# dac_blk.net
KiCad netlist of a schematic drawn in EAGLE
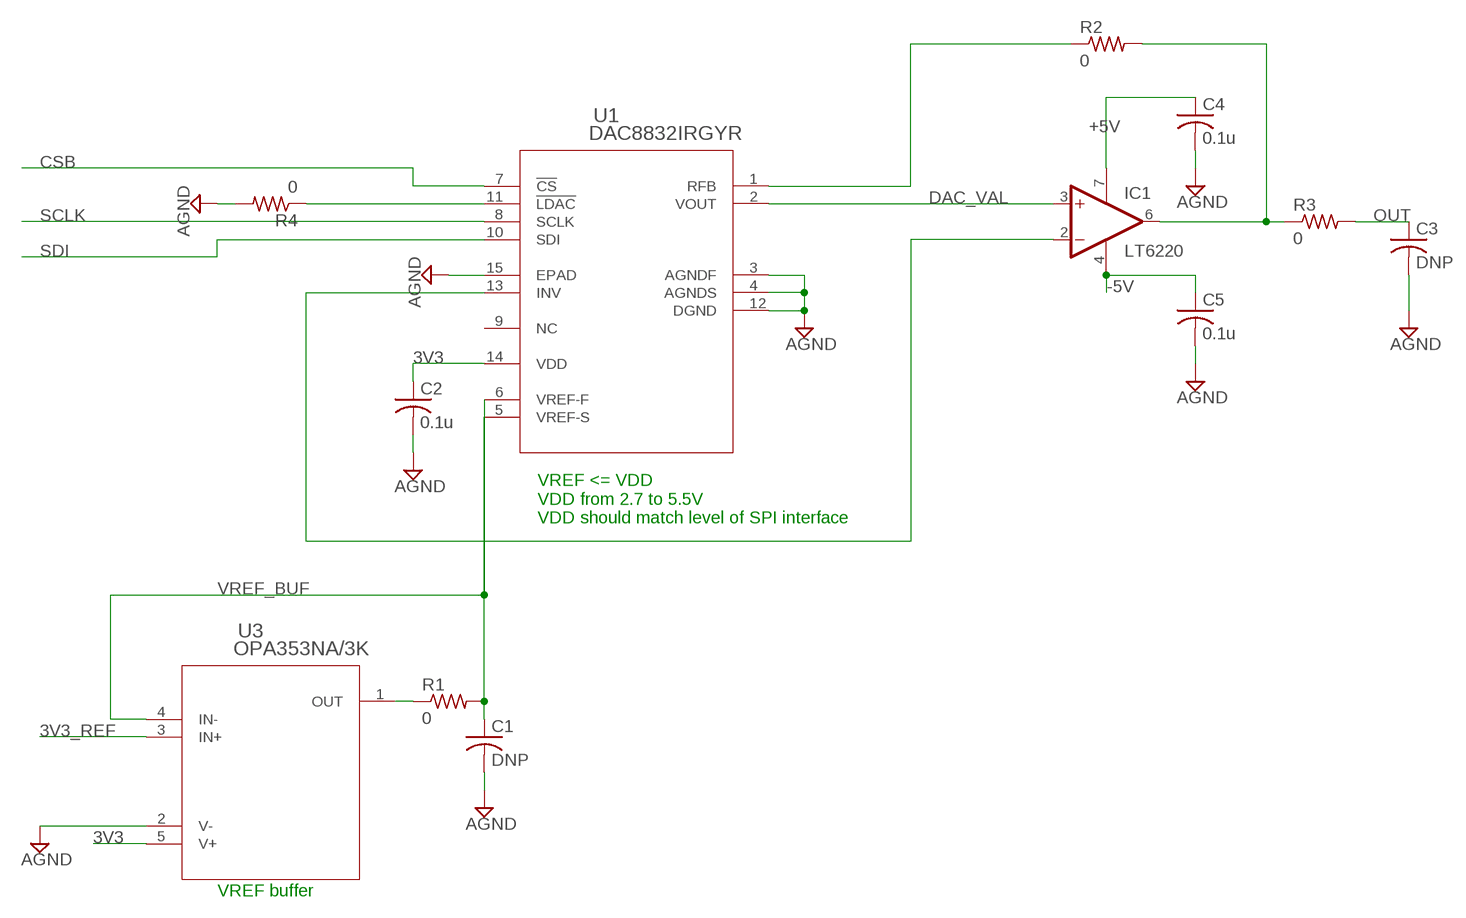
[diagram p0: schematic, sheet 1]

(export (version "E")
  (design (tool "Eeschema 10.0.6"))
  (components
    (comp (ref "C1")
      (value "DNP")
      (footprint "eagle-import:C0603")
      (libsource (lib "eagle-import") (part "C-USC0603"))
    )
    (comp (ref "C2")
      (value "0.1u")
      (footprint "eagle-import:C0603")
      (libsource (lib "eagle-import") (part "C-USC0603"))
    )
    (comp (ref "C3")
      (value "DNP")
      (footprint "eagle-import:C0603")
      (libsource (lib "eagle-import") (part "C-USC0603"))
    )
    (comp (ref "C4")
      (value "0.1u")
      (footprint "eagle-import:C0603")
      (libsource (lib "eagle-import") (part "C-USC0603"))
    )
    (comp (ref "C5")
      (value "0.1u")
      (footprint "eagle-import:C0603")
      (libsource (lib "eagle-import") (part "C-USC0603"))
    )
    (comp (ref "IC1")
      (value "LT6220")
      (footprint "eagle-import:SO08")
      (libsource (lib "eagle-import") (part "MCP601SN"))
    )
    (comp (ref "R1")
      (value "0")
      (footprint "eagle-import:R0603")
      (libsource (lib "eagle-import") (part "R-US_R0603"))
    )
    (comp (ref "R2")
      (value "0")
      (footprint "eagle-import:R0603")
      (libsource (lib "eagle-import") (part "R-US_R0603"))
    )
    (comp (ref "R3")
      (value "0")
      (footprint "eagle-import:R0603")
      (libsource (lib "eagle-import") (part "R-US_R0603"))
    )
    (comp (ref "R4")
      (value "0")
      (footprint "eagle-import:R0603")
      (libsource (lib "eagle-import") (part "R-US_R0603"))
    )
    (comp (ref "U1")
      (value "DAC8832IRGYR")
      (footprint "eagle-import:RGY14_2P05X2P05")
      (fields (field (name "MANUFACTURER") "Texas Instruments"))
      (libsource (lib "eagle-import") (part "DAC8832IRGYR"))
    )
    (comp (ref "U3")
      (value "OPA353NA/3K")
      (footprint "eagle-import:DBV5")
      (fields (field (name "MANUFACTURER") "Texas Instruments"))
      (libsource (lib "eagle-import") (part "OPA353NA/3K"))
    )
  )
  (nets
    (net (code "1") (name "/+5V") (class "Default")
      (node (ref "C4") (pin "1") (pinfunction "1_1") (pintype "passive"))
      (node (ref "IC1") (pin "7") (pinfunction "V+_7") (pintype "power_in"))
    )
    (net (code "2") (name "/-5V") (class "Default")
      (node (ref "C5") (pin "1") (pinfunction "1_1") (pintype "passive"))
      (node (ref "IC1") (pin "4") (pinfunction "V-_4") (pintype "power_in"))
    )
    (net (code "3") (name "/3V3") (class "Default")
      (node (ref "C2") (pin "1") (pinfunction "1_1") (pintype "passive"))
      (node (ref "U1") (pin "14") (pinfunction "VDD_14") (pintype "power_in"))
      (node (ref "U3") (pin "5") (pinfunction "V+_5") (pintype "power_in"))
    )
    (net (code "4") (name "/3V3_REF") (class "Default")
      (node (ref "U3") (pin "3") (pinfunction "IN+_3") (pintype "input"))
    )
    (net (code "5") (name "/CSB") (class "Default")
      (node (ref "U1") (pin "7") (pinfunction "~{CS}_7") (pintype "input"))
    )
    (net (code "6") (name "/DAC_VAL") (class "Default")
      (node (ref "IC1") (pin "3") (pinfunction "+IN_3") (pintype "input"))
      (node (ref "U1") (pin "2") (pinfunction "VOUT_2") (pintype "output"))
    )
    (net (code "7") (name "/N$2") (class "Default")
      (node (ref "IC1") (pin "2") (pinfunction "-IN_2") (pintype "input"))
      (node (ref "IC1") (pin "6") (pinfunction "OUT_6") (pintype "output"))
      (node (ref "R2") (pin "2") (pinfunction "2_2") (pintype "passive"))
      (node (ref "R3") (pin "1") (pinfunction "1_1") (pintype "passive"))
      (node (ref "U1") (pin "13") (pinfunction "INV_13") (pintype "passive"))
    )
    (net (code "8") (name "/OUT") (class "Default")
      (node (ref "C3") (pin "1") (pinfunction "1_1") (pintype "passive"))
      (node (ref "R3") (pin "2") (pinfunction "2_2") (pintype "passive"))
    )
    (net (code "9") (name "/SCLK") (class "Default")
      (node (ref "U1") (pin "8") (pinfunction "SCLK_8") (pintype "input"))
    )
    (net (code "10") (name "/SDI") (class "Default")
      (node (ref "U1") (pin "10") (pinfunction "SDI_10") (pintype "input"))
    )
    (net (code "11") (name "/VREF_BUF") (class "Default")
      (node (ref "C1") (pin "1") (pinfunction "1_1") (pintype "passive"))
      (node (ref "R1") (pin "2") (pinfunction "2_2") (pintype "passive"))
      (node (ref "U1") (pin "5") (pinfunction "VREF-S_5") (pintype "input"))
      (node (ref "U1") (pin "6") (pinfunction "VREF-F_6") (pintype "input"))
      (node (ref "U3") (pin "4") (pinfunction "IN-_4") (pintype "input"))
    )
    (net (code "12") (name "AGND") (class "Default")
      (node (ref "C1") (pin "2") (pinfunction "2_2") (pintype "passive"))
      (node (ref "C2") (pin "2") (pinfunction "2_2") (pintype "passive"))
      (node (ref "C3") (pin "2") (pinfunction "2_2") (pintype "passive"))
      (node (ref "C4") (pin "2") (pinfunction "2_2") (pintype "passive"))
      (node (ref "C5") (pin "2") (pinfunction "2_2") (pintype "passive"))
      (node (ref "R4") (pin "2") (pinfunction "2_2") (pintype "passive"))
      (node (ref "U1") (pin "12") (pinfunction "DGND_12") (pintype "power_in"))
      (node (ref "U1") (pin "15") (pinfunction "EPAD_15") (pintype "passive"))
      (node (ref "U1") (pin "3") (pinfunction "AGNDF_3") (pintype "power_in"))
      (node (ref "U1") (pin "4") (pinfunction "AGNDS_4") (pintype "power_in"))
      (node (ref "U3") (pin "2") (pinfunction "V-_2") (pintype "power_in"))
    )
    (net (code "13") (name "Net-(U1-RFB)") (class "Default")
      (node (ref "R2") (pin "1") (pinfunction "1_1") (pintype "passive"))
      (node (ref "U1") (pin "1") (pinfunction "RFB_1") (pintype "output"))
    )
    (net (code "14") (name "Net-(U1-~{LDAC})") (class "Default")
      (node (ref "R4") (pin "1") (pinfunction "1_1") (pintype "passive"))
      (node (ref "U1") (pin "11") (pinfunction "~{LDAC}_11") (pintype "input"))
    )
    (net (code "15") (name "Net-(U3-OUT)") (class "Default")
      (node (ref "R1") (pin "1") (pinfunction "1_1") (pintype "passive"))
      (node (ref "U3") (pin "1") (pinfunction "OUT_1") (pintype "output"))
    )
    (net (code "16") (name "unconnected-(U1-NC-Pad9)") (class "Default")
      (node (ref "U1") (pin "9") (pinfunction "NC_9") (pintype "passive"))
    )
  )
)
